# panel.net
KiCad netlist of a schematic drawn in Altium Designer
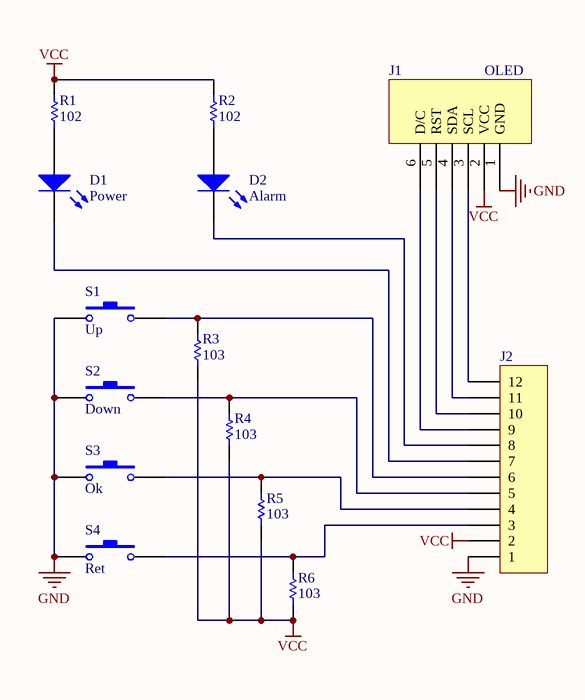
[diagram p0: panel.SchDoc]

(export (version "E")
  (design (tool "Eeschema 10.0.6"))
  (components
    (comp (ref "D1")
      (value "Power")
      (footprint "LED-2P")
      (description "Typical INFRARED GaAs LED")
      (fields (field (name "PUBLISHER") "*"))
      (libsource (lib "UC-MEGA128V1sch") (part "LED"))
    )
    (comp (ref "D2")
      (value "Alarm")
      (footprint "LED-2P")
      (description "Typical INFRARED GaAs LED")
      (fields (field (name "PUBLISHER") "*"))
      (libsource (lib "UC-MEGA128V1sch") (part "LED"))
    )
    (comp (ref "J1") (value "OLED") (footprint "OLED") (libsource (lib "newwind") (part "OLED")))
    (comp (ref "J2")
      (value "~")
      (footprint "XH2.54-12P")
      (description "Header, 12-Pin")
      (fields (field (name "PUBLISHER") "Altium Limited"))
      (libsource (lib "Miscellaneous Connectors") (part "Header 12"))
    )
    (comp (ref "R1")
      (value "102")
      (footprint "0805")
      (description "Resistor")
      (fields (field (name "PUBLISHER") "*"))
      (libsource (lib "UC-MEGA128V1sch") (part "Res"))
    )
    (comp (ref "R2")
      (value "102")
      (footprint "0805")
      (description "Resistor")
      (fields (field (name "PUBLISHER") "*"))
      (libsource (lib "UC-MEGA128V1sch") (part "Res"))
    )
    (comp (ref "R3")
      (value "103")
      (footprint "0805")
      (description "Resistor")
      (fields (field (name "PUBLISHER") "Altium Limited"))
      (libsource (lib "WeijaySch") (part "Res"))
    )
    (comp (ref "R4")
      (value "103")
      (footprint "0805")
      (description "Resistor")
      (fields (field (name "PUBLISHER") "Altium Limited"))
      (libsource (lib "WeijaySch") (part "Res"))
    )
    (comp (ref "R5")
      (value "103")
      (footprint "0805")
      (description "Resistor")
      (fields (field (name "PUBLISHER") "Altium Limited"))
      (libsource (lib "WeijaySch") (part "Res"))
    )
    (comp (ref "R6")
      (value "103")
      (footprint "0805")
      (description "Resistor")
      (fields (field (name "PUBLISHER") "Altium Limited"))
      (libsource (lib "WeijaySch") (part "Res"))
    )
    (comp (ref "S1")
      (value "Up")
      (footprint "SW-PB")
      (description "Switch")
      (fields (field (name "PUBLISHER") "*"))
      (libsource (lib "UC-MEGA128V1sch") (part "SW-PB"))
    )
    (comp (ref "S2")
      (value "Down")
      (footprint "SW-PB")
      (description "Switch")
      (fields (field (name "PUBLISHER") "*"))
      (libsource (lib "UC-MEGA128V1sch") (part "SW-PB"))
    )
    (comp (ref "S3")
      (value "Ok")
      (footprint "SW-PB")
      (description "Switch")
      (fields (field (name "PUBLISHER") "*"))
      (libsource (lib "UC-MEGA128V1sch") (part "SW-PB"))
    )
    (comp (ref "S4")
      (value "Ret")
      (footprint "SW-PB")
      (description "Switch")
      (fields (field (name "PUBLISHER") "*"))
      (libsource (lib "UC-MEGA128V1sch") (part "SW-PB"))
    )
  )
  (nets
    (net (code "1") (name "GND") (class "Default")
      (node (ref "J1") (pin "1") (pinfunction "GND_1") (pintype "passive"))
      (node (ref "J2") (pin "1") (pinfunction "1_1") (pintype "passive"))
      (node (ref "S1") (pin "1") (pinfunction "1_1") (pintype "passive"))
      (node (ref "S2") (pin "1") (pinfunction "1_1") (pintype "passive"))
      (node (ref "S3") (pin "1") (pinfunction "1_1") (pintype "passive"))
      (node (ref "S4") (pin "1") (pinfunction "1_1") (pintype "passive"))
    )
    (net (code "2") (name "Net-(D1-A)") (class "Default")
      (node (ref "D1") (pin "1") (pinfunction "A_1") (pintype "passive"))
      (node (ref "R1") (pin "2") (pinfunction "2_2") (pintype "passive"))
    )
    (net (code "3") (name "Net-(D1-K)") (class "Default")
      (node (ref "D1") (pin "2") (pinfunction "K_2") (pintype "passive"))
      (node (ref "J2") (pin "7") (pinfunction "7_7") (pintype "passive"))
    )
    (net (code "4") (name "Net-(D2-A)") (class "Default")
      (node (ref "D2") (pin "1") (pinfunction "A_1") (pintype "passive"))
      (node (ref "R2") (pin "1") (pinfunction "1_1") (pintype "passive"))
    )
    (net (code "5") (name "Net-(D2-K)") (class "Default")
      (node (ref "D2") (pin "2") (pinfunction "K_2") (pintype "passive"))
      (node (ref "J2") (pin "8") (pinfunction "8_8") (pintype "passive"))
    )
    (net (code "6") (name "Net-(J1-D{slash}C)") (class "Default")
      (node (ref "J1") (pin "6") (pinfunction "D/C_6") (pintype "passive"))
      (node (ref "J2") (pin "9") (pinfunction "9_9") (pintype "passive"))
    )
    (net (code "7") (name "Net-(J1-RST)") (class "Default")
      (node (ref "J1") (pin "5") (pinfunction "RST_5") (pintype "passive"))
      (node (ref "J2") (pin "10") (pinfunction "10_10") (pintype "passive"))
    )
    (net (code "8") (name "Net-(J1-SCL)") (class "Default")
      (node (ref "J1") (pin "3") (pinfunction "SCL_3") (pintype "passive"))
      (node (ref "J2") (pin "12") (pinfunction "12_12") (pintype "passive"))
    )
    (net (code "9") (name "Net-(J1-SDA)") (class "Default")
      (node (ref "J1") (pin "4") (pinfunction "SDA_4") (pintype "passive"))
      (node (ref "J2") (pin "11") (pinfunction "11_11") (pintype "passive"))
    )
    (net (code "10") (name "Net-(J2-Pad3)") (class "Default")
      (node (ref "J2") (pin "3") (pinfunction "3_3") (pintype "passive"))
      (node (ref "R6") (pin "2") (pinfunction "2_2") (pintype "passive"))
      (node (ref "S4") (pin "2") (pinfunction "2_2") (pintype "passive"))
    )
    (net (code "11") (name "Net-(J2-Pad4)") (class "Default")
      (node (ref "J2") (pin "4") (pinfunction "4_4") (pintype "passive"))
      (node (ref "R5") (pin "2") (pinfunction "2_2") (pintype "passive"))
      (node (ref "S3") (pin "2") (pinfunction "2_2") (pintype "passive"))
    )
    (net (code "12") (name "Net-(J2-Pad5)") (class "Default")
      (node (ref "J2") (pin "5") (pinfunction "5_5") (pintype "passive"))
      (node (ref "R4") (pin "2") (pinfunction "2_2") (pintype "passive"))
      (node (ref "S2") (pin "2") (pinfunction "2_2") (pintype "passive"))
    )
    (net (code "13") (name "Net-(J2-Pad6)") (class "Default")
      (node (ref "J2") (pin "6") (pinfunction "6_6") (pintype "passive"))
      (node (ref "R3") (pin "2") (pinfunction "2_2") (pintype "passive"))
      (node (ref "S1") (pin "2") (pinfunction "2_2") (pintype "passive"))
    )
    (net (code "14") (name "VCC") (class "Default")
      (node (ref "J1") (pin "2") (pinfunction "VCC_2") (pintype "passive"))
      (node (ref "J2") (pin "2") (pinfunction "2_2") (pintype "passive"))
      (node (ref "R1") (pin "1") (pinfunction "1_1") (pintype "passive"))
      (node (ref "R2") (pin "2") (pinfunction "2_2") (pintype "passive"))
      (node (ref "R3") (pin "1") (pinfunction "1_1") (pintype "passive"))
      (node (ref "R4") (pin "1") (pinfunction "1_1") (pintype "passive"))
      (node (ref "R5") (pin "1") (pinfunction "1_1") (pintype "passive"))
      (node (ref "R6") (pin "1") (pinfunction "1_1") (pintype "passive"))
    )
  )
)
